# R_N_Motor_Controller.net
KiCad netlist of a schematic drawn in EAGLE
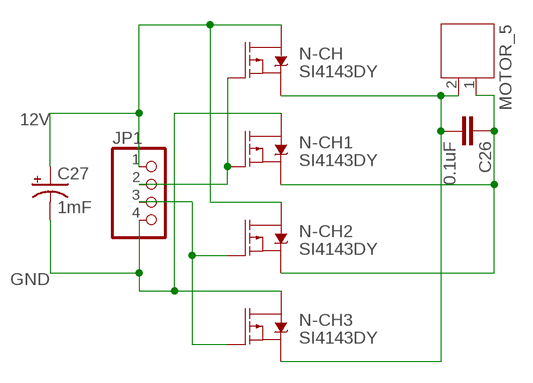
[diagram p0: schematic, sheet 1]

(export (version "E")
  (design (tool "Eeschema 10.0.6"))
  (components
    (comp (ref "C26")
      (value "0.1uF")
      (footprint "eagle-import:0603")
      (libsource (lib "eagle-import") (part "0.1UF-0603-25V-(+80/-20%)"))
    )
    (comp (ref "C27")
      (value "1mF")
      (footprint "eagle-import:CPOL-RADIAL-5MM-10MM")
      (libsource (lib "eagle-import") (part "1000UF-RADIAL-5MM-25V-20%"))
    )
    (comp (ref "JP1")
      (value "PINHD-1X4")
      (footprint "eagle-import:1X04")
      (libsource (lib "eagle-import") (part "PINHD-1X4"))
    )
    (comp (ref "MOTOR_5")
      (value "JST-PH2")
      (footprint "eagle-import:JST-PH2")
      (libsource (lib "eagle-import") (part "JST-PH2"))
    )
    (comp (ref "N-CH")
      (value "SI4143DY")
      (footprint "eagle-import:SO-8")
      (libsource (lib "eagle-import") (part "SI4143DY"))
    )
    (comp (ref "N-CH1")
      (value "SI4143DY")
      (footprint "eagle-import:SO-8")
      (libsource (lib "eagle-import") (part "SI4143DY"))
    )
    (comp (ref "N-CH2")
      (value "SI4143DY")
      (footprint "eagle-import:SO-8")
      (libsource (lib "eagle-import") (part "SI4143DY"))
    )
    (comp (ref "N-CH3")
      (value "SI4143DY")
      (footprint "eagle-import:SO-8")
      (libsource (lib "eagle-import") (part "SI4143DY"))
    )
  )
  (nets
    (net (code "1") (name "/12V") (class "Default")
      (node (ref "C27") (pin "+") (pinfunction "+_+") (pintype "passive"))
      (node (ref "JP1") (pin "1") (pinfunction "1_1") (pintype "passive"))
      (node (ref "N-CH") (pin "5") (pinfunction "D_5") (pintype "bidirectional"))
      (node (ref "N-CH") (pin "6") (pinfunction "D_6") (pintype "bidirectional"))
      (node (ref "N-CH") (pin "7") (pinfunction "D_7") (pintype "bidirectional"))
      (node (ref "N-CH") (pin "8") (pinfunction "D_8") (pintype "bidirectional"))
      (node (ref "N-CH2") (pin "5") (pinfunction "D_5") (pintype "bidirectional"))
      (node (ref "N-CH2") (pin "6") (pinfunction "D_6") (pintype "bidirectional"))
      (node (ref "N-CH2") (pin "7") (pinfunction "D_7") (pintype "bidirectional"))
      (node (ref "N-CH2") (pin "8") (pinfunction "D_8") (pintype "bidirectional"))
    )
    (net (code "2") (name "/GND") (class "Default")
      (node (ref "C27") (pin "-") (pinfunction "-_-") (pintype "passive"))
      (node (ref "JP1") (pin "4") (pinfunction "4_4") (pintype "passive"))
      (node (ref "N-CH1") (pin "5") (pinfunction "D_5") (pintype "bidirectional"))
      (node (ref "N-CH1") (pin "6") (pinfunction "D_6") (pintype "bidirectional"))
      (node (ref "N-CH1") (pin "7") (pinfunction "D_7") (pintype "bidirectional"))
      (node (ref "N-CH1") (pin "8") (pinfunction "D_8") (pintype "bidirectional"))
      (node (ref "N-CH3") (pin "5") (pinfunction "D_5") (pintype "bidirectional"))
      (node (ref "N-CH3") (pin "6") (pinfunction "D_6") (pintype "bidirectional"))
      (node (ref "N-CH3") (pin "7") (pinfunction "D_7") (pintype "bidirectional"))
      (node (ref "N-CH3") (pin "8") (pinfunction "D_8") (pintype "bidirectional"))
    )
    (net (code "3") (name "Net-(C26-Pad1)") (class "Default")
      (node (ref "C26") (pin "1") (pinfunction "1_1") (pintype "passive"))
      (node (ref "MOTOR_5") (pin "1") (pinfunction "1_1") (pintype "passive"))
      (node (ref "N-CH1") (pin "1") (pinfunction "S_1") (pintype "bidirectional"))
      (node (ref "N-CH1") (pin "2") (pinfunction "S_2") (pintype "bidirectional"))
      (node (ref "N-CH1") (pin "3") (pinfunction "S_3") (pintype "bidirectional"))
      (node (ref "N-CH2") (pin "1") (pinfunction "S_1") (pintype "bidirectional"))
      (node (ref "N-CH2") (pin "2") (pinfunction "S_2") (pintype "bidirectional"))
      (node (ref "N-CH2") (pin "3") (pinfunction "S_3") (pintype "bidirectional"))
    )
    (net (code "4") (name "Net-(C26-Pad2)") (class "Default")
      (node (ref "C26") (pin "2") (pinfunction "2_2") (pintype "passive"))
      (node (ref "MOTOR_5") (pin "2") (pinfunction "2_2") (pintype "passive"))
      (node (ref "N-CH") (pin "1") (pinfunction "S_1") (pintype "bidirectional"))
      (node (ref "N-CH") (pin "2") (pinfunction "S_2") (pintype "bidirectional"))
      (node (ref "N-CH") (pin "3") (pinfunction "S_3") (pintype "bidirectional"))
      (node (ref "N-CH3") (pin "1") (pinfunction "S_1") (pintype "bidirectional"))
      (node (ref "N-CH3") (pin "2") (pinfunction "S_2") (pintype "bidirectional"))
      (node (ref "N-CH3") (pin "3") (pinfunction "S_3") (pintype "bidirectional"))
    )
    (net (code "5") (name "Net-(N-CH-G)") (class "Default")
      (node (ref "JP1") (pin "2") (pinfunction "2_2") (pintype "passive"))
      (node (ref "N-CH") (pin "4") (pinfunction "G_4") (pintype "bidirectional"))
      (node (ref "N-CH1") (pin "4") (pinfunction "G_4") (pintype "bidirectional"))
    )
    (net (code "6") (name "Net-(N-CH2-G)") (class "Default")
      (node (ref "JP1") (pin "3") (pinfunction "3_3") (pintype "passive"))
      (node (ref "N-CH2") (pin "4") (pinfunction "G_4") (pintype "bidirectional"))
      (node (ref "N-CH3") (pin "4") (pinfunction "G_4") (pintype "bidirectional"))
    )
  )
)
